# UART_TO_USB.net
KiCad netlist of a schematic drawn in Altium Designer
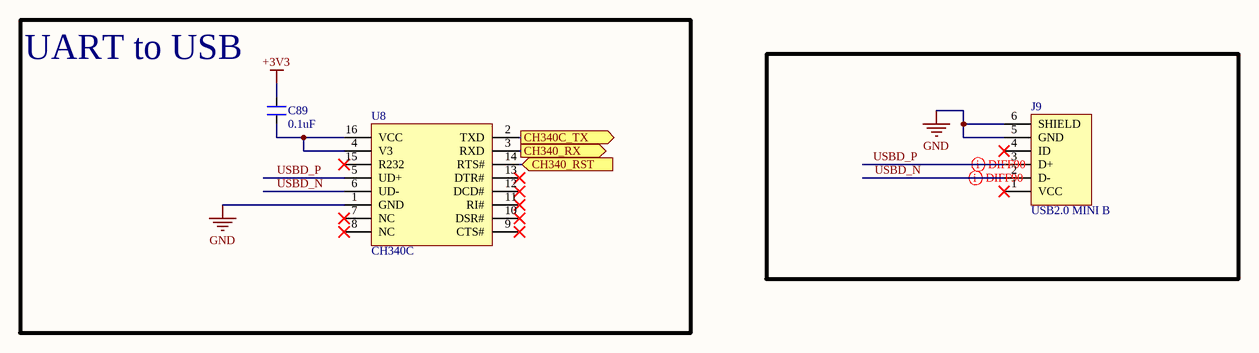
[diagram p0: UART TO USB.SchDoc]

(export (version "E")
  (design (tool "Eeschema 10.0.6"))
  (components
    (comp (ref "C89")
      (value "0.1uF")
      (footprint "CAP_0805")
      (description "0.1µF ±10% 50V Ceramic Capacitor X7R 0805 (2012 Metric)")
      (fields
        (field (name "MANUFACTURER") "Samsung")
        (field (name "MANUFACTURER PART NUMBER") "CL21B104KBCNNNC")
      )
      (libsource (lib "ESTEEMPCBLIB") (part "CAP_0.1uF-50V-10%-0805"))
    )
    (comp (ref "J9")
      (value "USB2.0 MINI B")
      (footprint "CON_690-005-299-043")
      (description "USB - mini B USB 2.0 Receptacle Connector 5 Position Surface Mount, Right Angle")
      (fields
        (field (name "MANUFACTURER") "EDAC")
        (field (name "MANUFACTURER PART NUMBER") "690-005-299-043")
      )
      (libsource (lib "ESTEEMPCBLIB") (part "CON_USB2.0-MINIB-SMD"))
    )
    (comp (ref "U8")
      (value "CH340C")
      (footprint "SOIC16_50_284_25X90_SMT")
      (description "USB Bridge, USB to UART USB 2.0 UART Interface")
      (fields (field (name "MANUFACTURER") "Olimex"))
      (libsource (lib "ESTEEMPCBLIB") (part "IC_CH340C"))
    )
  )
  (nets
    (net (code "1") (name "+3V3") (class "Default")
      (node (ref "C89") (pin "2") (pinfunction "2_2") (pintype "passive"))
    )
    (net (code "2") (name "/CH340C_TX") (class "Default")
      (node (ref "U8") (pin "2") (pinfunction "TXD_2") (pintype "passive"))
    )
    (net (code "3") (name "/CH340_RST") (class "Default")
      (node (ref "U8") (pin "14") (pinfunction "RTS#_14") (pintype "passive"))
    )
    (net (code "4") (name "/CH340_RX") (class "Default")
      (node (ref "U8") (pin "3") (pinfunction "RXD_3") (pintype "passive"))
    )
    (net (code "5") (name "/USBD_N") (class "Default")
      (node (ref "J9") (pin "2") (pinfunction "D-_2") (pintype "passive"))
      (node (ref "U8") (pin "6") (pinfunction "UD-_6") (pintype "passive"))
    )
    (net (code "6") (name "/USBD_P") (class "Default")
      (node (ref "J9") (pin "3") (pinfunction "D+_3") (pintype "passive"))
      (node (ref "U8") (pin "5") (pinfunction "UD+_5") (pintype "passive"))
    )
    (net (code "7") (name "GND") (class "Default")
      (node (ref "J9") (pin "5") (pinfunction "GND_5") (pintype "passive"))
      (node (ref "J9") (pin "6") (pinfunction "SHIELD_6") (pintype "passive"))
      (node (ref "U8") (pin "1") (pinfunction "GND_1") (pintype "passive"))
    )
    (net (code "8") (name "Net-(U8-V3)") (class "Default")
      (node (ref "C89") (pin "1") (pinfunction "1_1") (pintype "passive"))
      (node (ref "U8") (pin "16") (pinfunction "VCC_16") (pintype "passive"))
      (node (ref "U8") (pin "4") (pinfunction "V3_4") (pintype "passive"))
    )
    (net (code "9") (name "unconnected-(J9-ID-Pad4)") (class "Default")
      (node (ref "J9") (pin "4") (pinfunction "ID_4") (pintype "passive+no_connect"))
    )
    (net (code "10") (name "unconnected-(J9-VCC-Pad1)") (class "Default")
      (node (ref "J9") (pin "1") (pinfunction "VCC_1") (pintype "passive+no_connect"))
    )
    (net (code "11") (name "unconnected-(U8-CTS#-Pad9)") (class "Default")
      (node (ref "U8") (pin "9") (pinfunction "CTS#_9") (pintype "passive+no_connect"))
    )
    (net (code "12") (name "unconnected-(U8-DCD#-Pad12)") (class "Default")
      (node (ref "U8") (pin "12") (pinfunction "DCD#_12") (pintype "passive+no_connect"))
    )
    (net (code "13") (name "unconnected-(U8-DSR#-Pad10)") (class "Default")
      (node (ref "U8") (pin "10") (pinfunction "DSR#_10") (pintype "passive+no_connect"))
    )
    (net (code "14") (name "unconnected-(U8-DTR#-Pad13)") (class "Default")
      (node (ref "U8") (pin "13") (pinfunction "DTR#_13") (pintype "passive+no_connect"))
    )
    (net (code "15") (name "unconnected-(U8-NC-Pad7)") (class "Default")
      (node (ref "U8") (pin "7") (pinfunction "NC_7") (pintype "passive+no_connect"))
    )
    (net (code "16") (name "unconnected-(U8-NC-Pad8)") (class "Default")
      (node (ref "U8") (pin "8") (pinfunction "NC_8") (pintype "passive+no_connect"))
    )
    (net (code "17") (name "unconnected-(U8-R232-Pad15)") (class "Default")
      (node (ref "U8") (pin "15") (pinfunction "R232_15") (pintype "passive+no_connect"))
    )
    (net (code "18") (name "unconnected-(U8-RI#-Pad11)") (class "Default")
      (node (ref "U8") (pin "11") (pinfunction "RI#_11") (pintype "passive+no_connect"))
    )
  )
)
